# RLCD_SCH_28LED_v1p13p2.net
KiCad netlist of a schematic drawn in EAGLE
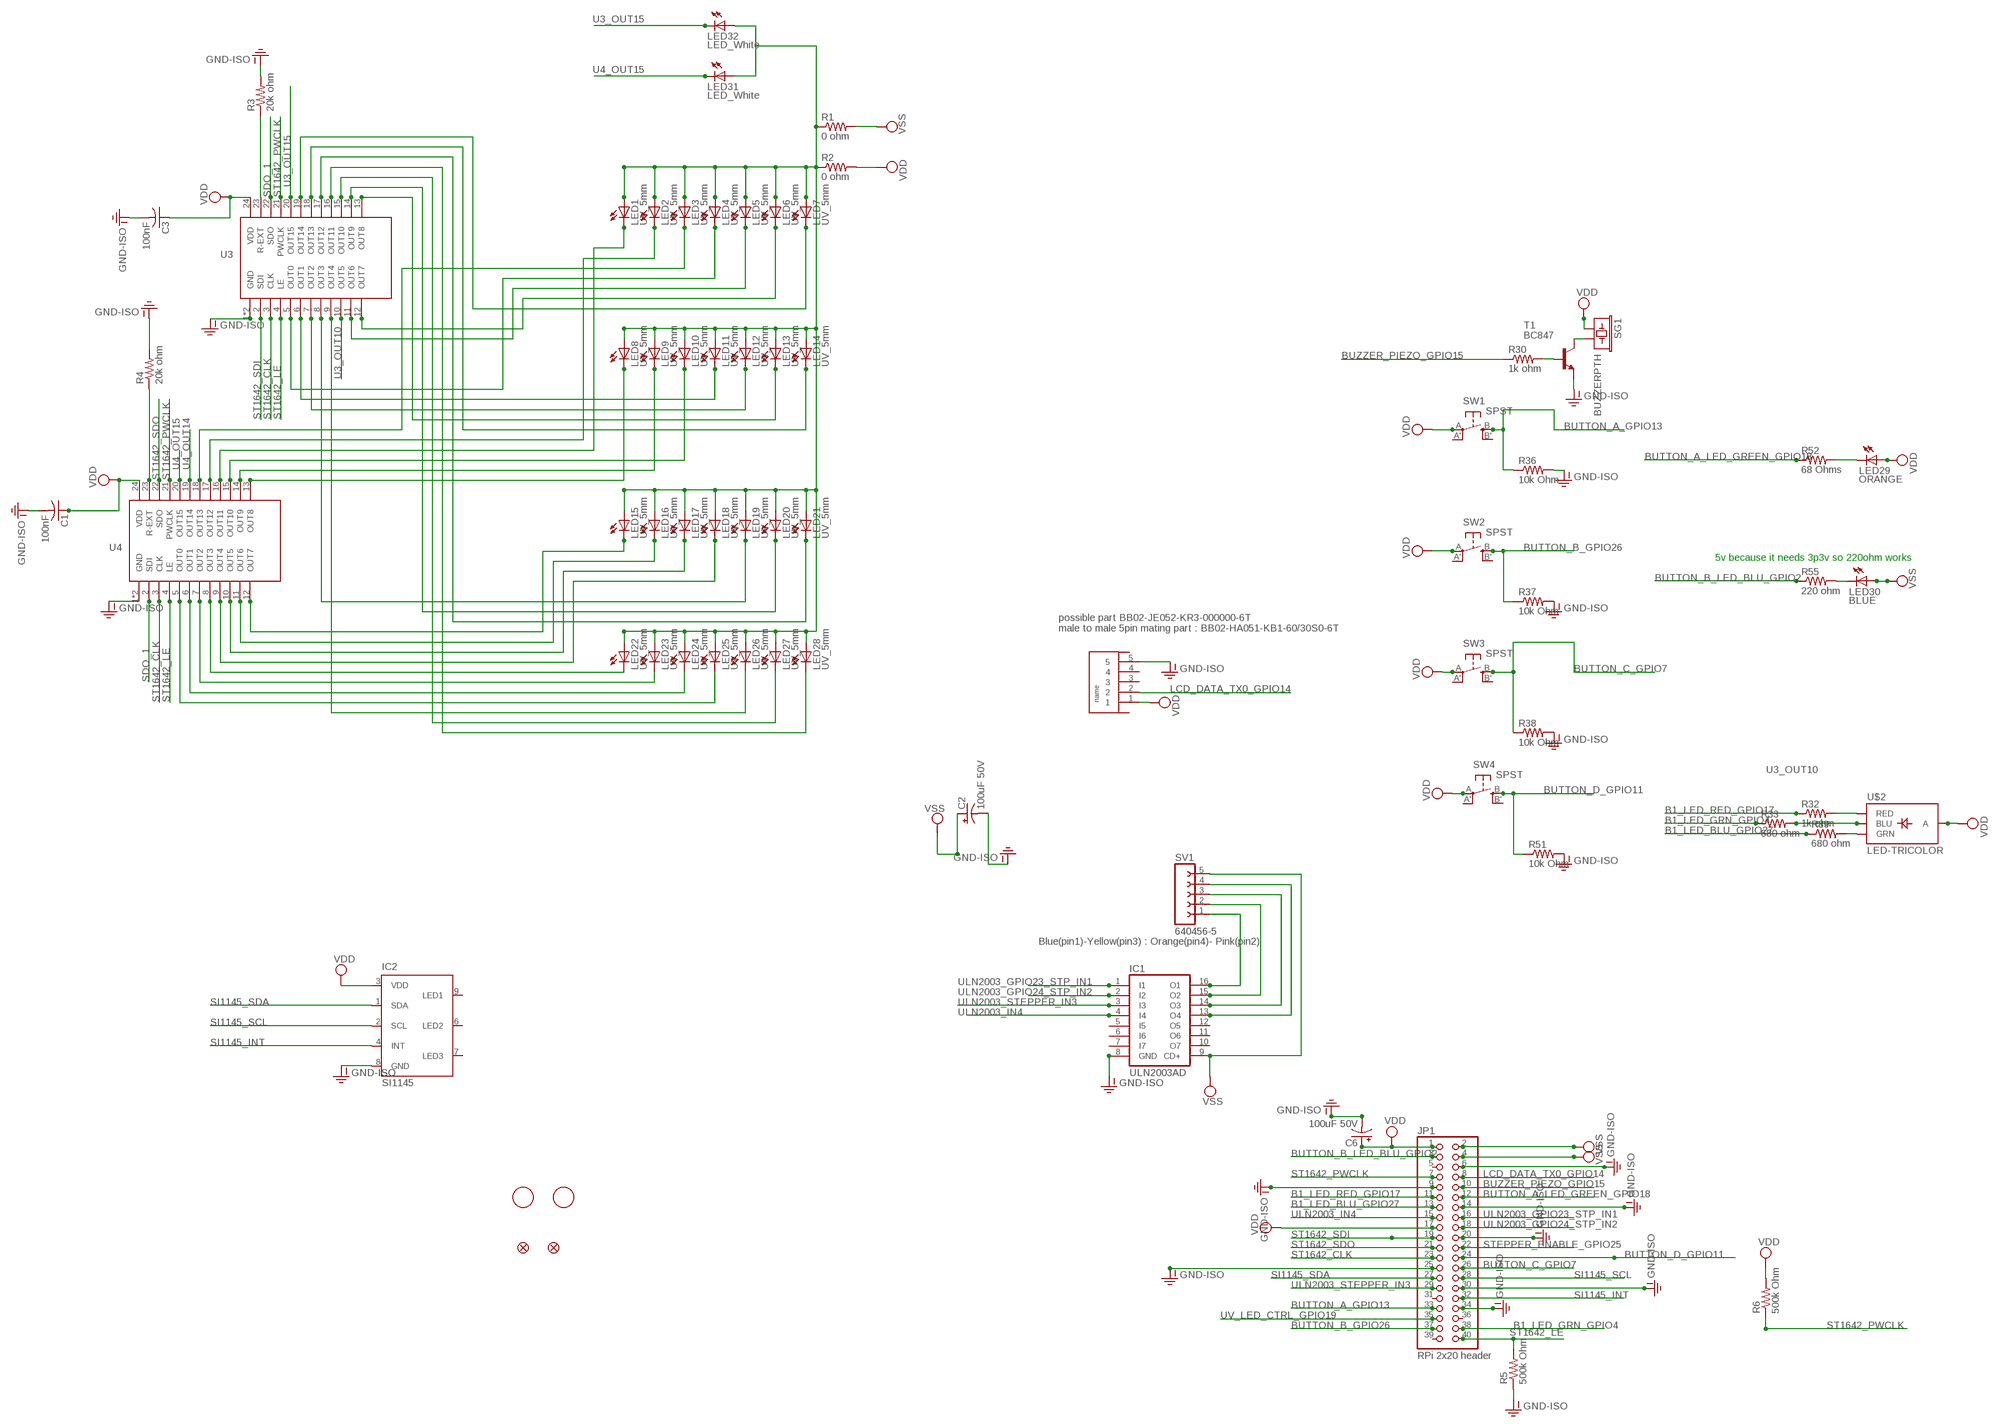
[diagram p0: schematic, sheet 1]

(export (version "E")
  (design (tool "Eeschema 10.0.6"))
  (components
    (comp (ref "C1")
      (value "100nF")
      (footprint "eagle-import:C0805")
      (libsource (lib "eagle-import") (part "C-USC0805"))
    )
    (comp (ref "C2")
      (value "100uF 50V")
      (footprint "eagle-import:E3,5-8")
      (fields (field (name "PARTNO") "REA101M1HBK-0811P"))
      (libsource (lib "eagle-import") (part "CPOL-USE3.5-8"))
    )
    (comp (ref "C3")
      (value "100nF")
      (footprint "eagle-import:C0805")
      (libsource (lib "eagle-import") (part "C-USC0805"))
    )
    (comp (ref "C6")
      (value "100uF 50V")
      (footprint "eagle-import:E3,5-8")
      (fields (field (name "PARTNO") "REA101M1HBK-0811P"))
      (libsource (lib "eagle-import") (part "CPOL-USE3.5-8"))
    )
    (comp (ref "FID1")
      (value "FIDUCIAL1X2")
      (footprint "eagle-import:FIDUCIAL-1X2")
      (libsource (lib "eagle-import") (part "FIDUCIAL1X2"))
    )
    (comp (ref "FID2")
      (value "FIDUCIAL1X2")
      (footprint "eagle-import:FIDUCIAL-1X2")
      (libsource (lib "eagle-import") (part "FIDUCIAL1X2"))
    )
    (comp (ref "IC1")
      (value "ULN2003AD")
      (footprint "eagle-import:SO16")
      (libsource (lib "eagle-import") (part "ULN2003AD"))
    )
    (comp (ref "IC2")
      (value "SI1145")
      (footprint "eagle-import:QFN-10")
      (libsource (lib "eagle-import") (part "SI1145"))
    )
    (comp (ref "JP1")
      (value "RPi 2x20 header")
      (footprint "eagle-import:2X20")
      (fields (field (name "PARTNO") "929975-01-13-RK"))
      (libsource (lib "eagle-import") (part "PINHD-2X20"))
    )
    (comp (ref "LED1")
      (value "UV_5mm")
      (footprint "eagle-import:LED5MM")
      (libsource (lib "eagle-import") (part "led_LED5MM"))
    )
    (comp (ref "LED2")
      (value "UV_5mm")
      (footprint "eagle-import:LED5MM")
      (libsource (lib "eagle-import") (part "led_LED5MM"))
    )
    (comp (ref "LED3")
      (value "UV_5mm")
      (footprint "eagle-import:LED5MM")
      (libsource (lib "eagle-import") (part "led_LED5MM"))
    )
    (comp (ref "LED4")
      (value "UV_5mm")
      (footprint "eagle-import:LED5MM")
      (libsource (lib "eagle-import") (part "led_LED5MM"))
    )
    (comp (ref "LED5")
      (value "UV_5mm")
      (footprint "eagle-import:LED5MM")
      (libsource (lib "eagle-import") (part "led_LED5MM"))
    )
    (comp (ref "LED6")
      (value "UV_5mm")
      (footprint "eagle-import:LED5MM")
      (libsource (lib "eagle-import") (part "led_LED5MM"))
    )
    (comp (ref "LED7")
      (value "UV_5mm")
      (footprint "eagle-import:LED5MM")
      (libsource (lib "eagle-import") (part "led_LED5MM"))
    )
    (comp (ref "LED8")
      (value "UV_5mm")
      (footprint "eagle-import:LED5MM")
      (libsource (lib "eagle-import") (part "led_LED5MM"))
    )
    (comp (ref "LED9")
      (value "UV_5mm")
      (footprint "eagle-import:LED5MM")
      (libsource (lib "eagle-import") (part "led_LED5MM"))
    )
    (comp (ref "LED10")
      (value "UV_5mm")
      (footprint "eagle-import:LED5MM")
      (libsource (lib "eagle-import") (part "led_LED5MM"))
    )
    (comp (ref "LED11")
      (value "UV_5mm")
      (footprint "eagle-import:LED5MM")
      (libsource (lib "eagle-import") (part "led_LED5MM"))
    )
    (comp (ref "LED12")
      (value "UV_5mm")
      (footprint "eagle-import:LED5MM")
      (libsource (lib "eagle-import") (part "led_LED5MM"))
    )
    (comp (ref "LED13")
      (value "UV_5mm")
      (footprint "eagle-import:LED5MM")
      (libsource (lib "eagle-import") (part "led_LED5MM"))
    )
    (comp (ref "LED14")
      (value "UV_5mm")
      (footprint "eagle-import:LED5MM")
      (libsource (lib "eagle-import") (part "led_LED5MM"))
    )
    (comp (ref "LED15")
      (value "UV_5mm")
      (footprint "eagle-import:LED5MM")
      (libsource (lib "eagle-import") (part "led_LED5MM"))
    )
    (comp (ref "LED16")
      (value "UV_5mm")
      (footprint "eagle-import:LED5MM")
      (libsource (lib "eagle-import") (part "led_LED5MM"))
    )
    (comp (ref "LED17")
      (value "UV_5mm")
      (footprint "eagle-import:LED5MM")
      (libsource (lib "eagle-import") (part "led_LED5MM"))
    )
    (comp (ref "LED18")
      (value "UV_5mm")
      (footprint "eagle-import:LED5MM")
      (libsource (lib "eagle-import") (part "led_LED5MM"))
    )
    (comp (ref "LED19")
      (value "UV_5mm")
      (footprint "eagle-import:LED5MM")
      (libsource (lib "eagle-import") (part "led_LED5MM"))
    )
    (comp (ref "LED20")
      (value "UV_5mm")
      (footprint "eagle-import:LED5MM")
      (libsource (lib "eagle-import") (part "led_LED5MM"))
    )
    (comp (ref "LED21")
      (value "UV_5mm")
      (footprint "eagle-import:LED5MM")
      (libsource (lib "eagle-import") (part "led_LED5MM"))
    )
    (comp (ref "LED22")
      (value "UV_5mm")
      (footprint "eagle-import:LED5MM")
      (libsource (lib "eagle-import") (part "led_LED5MM"))
    )
    (comp (ref "LED23")
      (value "UV_5mm")
      (footprint "eagle-import:LED5MM")
      (libsource (lib "eagle-import") (part "led_LED5MM"))
    )
    (comp (ref "LED24")
      (value "UV_5mm")
      (footprint "eagle-import:LED5MM")
      (libsource (lib "eagle-import") (part "led_LED5MM"))
    )
    (comp (ref "LED25")
      (value "UV_5mm")
      (footprint "eagle-import:LED5MM")
      (libsource (lib "eagle-import") (part "led_LED5MM"))
    )
    (comp (ref "LED26")
      (value "UV_5mm")
      (footprint "eagle-import:LED5MM")
      (libsource (lib "eagle-import") (part "led_LED5MM"))
    )
    (comp (ref "LED27")
      (value "UV_5mm")
      (footprint "eagle-import:LED5MM")
      (libsource (lib "eagle-import") (part "led_LED5MM"))
    )
    (comp (ref "LED28")
      (value "UV_5mm")
      (footprint "eagle-import:LED5MM")
      (libsource (lib "eagle-import") (part "led_LED5MM"))
    )
    (comp (ref "LED29")
      (value "ORANGE")
      (footprint "eagle-import:CHIPLED_1206")
      (fields (field (name "PARTNO") "LG N971-KN-1"))
      (libsource (lib "eagle-import") (part "LEDCHIPLED_1206"))
    )
    (comp (ref "LED30")
      (value "BLUE")
      (footprint "eagle-import:CHIPLED_1206")
      (fields (field (name "PARTNO") "LTST-C21TBKT"))
      (libsource (lib "eagle-import") (part "LEDCHIPLED_1206"))
    )
    (comp (ref "LED31")
      (value "LED_White")
      (footprint "eagle-import:CHIPLED_1206")
      (fields (field (name "PARTNO") "LG N971-KN-1"))
      (libsource (lib "eagle-import") (part "LEDCHIPLED_1206"))
    )
    (comp (ref "LED32")
      (value "LED_White")
      (footprint "eagle-import:CHIPLED_1206")
      (fields (field (name "PARTNO") "LG N971-KN-1"))
      (libsource (lib "eagle-import") (part "LEDCHIPLED_1206"))
    )
    (comp (ref "R1")
      (value "0 ohm")
      (footprint "eagle-import:0805")
      (fields (field (name "PARTNO") "DNP"))
      (libsource (lib "eagle-import") (part "RESISTOR0805-RES"))
    )
    (comp (ref "R2")
      (value "0 ohm")
      (footprint "eagle-import:0805")
      (fields (field (name "PARTNO") "DNP"))
      (libsource (lib "eagle-import") (part "RESISTOR0805-RES"))
    )
    (comp (ref "R3")
      (value "20k ohm")
      (footprint "eagle-import:0805")
      (fields (field (name "PARTNO") "DNP"))
      (libsource (lib "eagle-import") (part "RESISTOR0805-RES"))
    )
    (comp (ref "R4")
      (value "20k ohm")
      (footprint "eagle-import:0805")
      (fields (field (name "PARTNO") "DNP"))
      (libsource (lib "eagle-import") (part "RESISTOR0805-RES"))
    )
    (comp (ref "R5")
      (value "500k Ohm")
      (footprint "eagle-import:0805")
      (fields (field (name "PARTNO") "RK73B2ATTD103J"))
      (libsource (lib "eagle-import") (part "RESISTOR0805-RES"))
    )
    (comp (ref "R6")
      (value "500k Ohm")
      (footprint "eagle-import:0805")
      (fields (field (name "PARTNO") "RK73B2ATTD103J"))
      (libsource (lib "eagle-import") (part "RESISTOR0805-RES"))
    )
    (comp (ref "R30")
      (value "1k ohm")
      (footprint "eagle-import:0805")
      (fields (field (name "PARTNO") "RK73H2ATTD1001F"))
      (libsource (lib "eagle-import") (part "RESISTOR0805-RES"))
    )
    (comp (ref "R32")
      (value "1k ohm")
      (footprint "eagle-import:0805")
      (fields (field (name "PARTNO") "RK73H2ATTD1001F"))
      (libsource (lib "eagle-import") (part "RESISTOR0805-RES"))
    )
    (comp (ref "R33")
      (value "680 ohm")
      (footprint "eagle-import:0805")
      (fields (field (name "PARTNO") "RK73B2ATTD681J"))
      (libsource (lib "eagle-import") (part "RESISTOR0805-RES"))
    )
    (comp (ref "R36")
      (value "10k Ohm")
      (footprint "eagle-import:0805")
      (fields (field (name "PARTNO") "RK73B2ATTD103J"))
      (libsource (lib "eagle-import") (part "RESISTOR0805-RES"))
    )
    (comp (ref "R37")
      (value "10k Ohm")
      (footprint "eagle-import:0805")
      (fields (field (name "PARTNO") "RK73B2ATTD103J"))
      (libsource (lib "eagle-import") (part "RESISTOR0805-RES"))
    )
    (comp (ref "R38")
      (value "10k Ohm")
      (footprint "eagle-import:0805")
      (fields (field (name "PARTNO") "RK73B2ATTD103J"))
      (libsource (lib "eagle-import") (part "RESISTOR0805-RES"))
    )
    (comp (ref "R39")
      (value "680 ohm")
      (footprint "eagle-import:0805")
      (fields (field (name "PARTNO") "RK73B2ATTD681J"))
      (libsource (lib "eagle-import") (part "RESISTOR0805-RES"))
    )
    (comp (ref "R51")
      (value "10k Ohm")
      (footprint "eagle-import:0805")
      (fields (field (name "PARTNO") "RK73B2ATTD103J"))
      (libsource (lib "eagle-import") (part "RESISTOR0805-RES"))
    )
    (comp (ref "R52")
      (value "68 Ohms")
      (footprint "eagle-import:0805")
      (fields (field (name "PARTNO") "RK73B2ATTDD121J"))
      (libsource (lib "eagle-import") (part "RESISTOR0805-RES"))
    )
    (comp (ref "R55")
      (value "220 ohm")
      (footprint "eagle-import:0805")
      (fields (field (name "PARTNO") "RK73B2ATTD221J"))
      (libsource (lib "eagle-import") (part "RESISTOR0805-RES"))
    )
    (comp (ref "SG1")
      (value "BUZZERPTH")
      (footprint "eagle-import:BUZZER-12MM")
      (fields (field (name "PARTNO") "AT-1220-TT-R"))
      (libsource (lib "eagle-import") (part "BUZZERPTH"))
    )
    (comp (ref "SV1")
      (value "640456-5")
      (footprint "eagle-import:FE05-1")
      (libsource (lib "eagle-import") (part "FE05-1"))
    )
    (comp (ref "SV3_LCD_HEADER")
      (value "22-05-2051")
      (footprint "eagle-import:MDF7-5S-2.54DSA")
      (fields (field (name "PARTNO") "MDF7-5S-2.54DSA(55)"))
      (libsource (lib "eagle-import") (part "MDF7-5S-2.54DSA"))
    )
    (comp (ref "SW1")
      (value "SPST")
      (footprint "eagle-import:EVQ-Q2")
      (libsource (lib "eagle-import") (part "SPST_TACT-EVQQ2"))
    )
    (comp (ref "SW2")
      (value "SPST")
      (footprint "eagle-import:EVQ-Q2")
      (libsource (lib "eagle-import") (part "SPST_TACT-EVQQ2"))
    )
    (comp (ref "SW3")
      (value "SPST")
      (footprint "eagle-import:EVQ-Q2")
      (libsource (lib "eagle-import") (part "SPST_TACT-EVQQ2"))
    )
    (comp (ref "SW4")
      (value "SPST")
      (footprint "eagle-import:EVQ-Q2")
      (libsource (lib "eagle-import") (part "SPST_TACT-EVQQ2"))
    )
    (comp (ref "T1")
      (value "BC847")
      (footprint "eagle-import:SOT23")
      (fields (field (name "PARTNO") "MMUN2214LT1G"))
      (libsource (lib "eagle-import") (part "BC847"))
    )
    (comp (ref "U$1")
      (value "FIDUCIAL")
      (footprint "eagle-import:FIDUCIAL_1MM")
      (libsource (lib "eagle-import") (part "FIDUCIAL"))
    )
    (comp (ref "U$2")
      (value "LED-TRICOLOR")
      (footprint "eagle-import:LED-TRICOLOR-SMD")
      (fields (field (name "PARTNO") "CLV1A-FKB-CHMKPEHBB7A363"))
      (libsource (lib "eagle-import") (part "LED-TRICOLOR"))
    )
    (comp (ref "U$3")
      (value "LED1642GWTTR")
      (footprint "eagle-import:TSSOP24")
      (libsource (lib "eagle-import") (part "LED1642GWTTR"))
    )
    (comp (ref "U$4")
      (value "LED1642GWTTR")
      (footprint "eagle-import:TSSOP24")
      (libsource (lib "eagle-import") (part "LED1642GWTTR"))
    )
    (comp (ref "U$5")
      (value "FIDUCIAL")
      (footprint "eagle-import:FIDUCIAL_1MM")
      (libsource (lib "eagle-import") (part "FIDUCIAL"))
    )
  )
  (nets
    (net (code "1") (name "/B1_LED_BLU_GPIO27") (class "Default")
      (node (ref "JP1") (pin "13") (pinfunction "13_13") (pintype "passive"))
      (node (ref "R39") (pin "1") (pinfunction "1_1") (pintype "passive"))
    )
    (net (code "2") (name "/B1_LED_GRN_GPIO4") (class "Default")
      (node (ref "JP1") (pin "38") (pinfunction "38_38") (pintype "passive"))
      (node (ref "R33") (pin "1") (pinfunction "1_1") (pintype "passive"))
    )
    (net (code "3") (name "/B1_LED_RED_GPIO17") (class "Default")
      (node (ref "JP1") (pin "11") (pinfunction "11_11") (pintype "passive"))
      (node (ref "R32") (pin "1") (pinfunction "1_1") (pintype "passive"))
    )
    (net (code "4") (name "/BUTTON_A_GPIO13") (class "Default")
      (node (ref "JP1") (pin "33") (pinfunction "33_33") (pintype "passive"))
      (node (ref "R36") (pin "1") (pinfunction "1_1") (pintype "passive"))
      (node (ref "SW1") (pin "B") (pinfunction "S_B") (pintype "passive"))
    )
    (net (code "5") (name "/BUTTON_A_LED_GREEN_GPIO18") (class "Default")
      (node (ref "JP1") (pin "12") (pinfunction "12_12") (pintype "passive"))
      (node (ref "R52") (pin "1") (pinfunction "1_1") (pintype "passive"))
    )
    (net (code "6") (name "/BUTTON_B_GPIO26") (class "Default")
      (node (ref "JP1") (pin "37") (pinfunction "37_37") (pintype "passive"))
      (node (ref "R37") (pin "1") (pinfunction "1_1") (pintype "passive"))
      (node (ref "SW2") (pin "B") (pinfunction "S_B") (pintype "passive"))
    )
    (net (code "7") (name "/BUTTON_B_LED_BLU_GPIO2") (class "Default")
      (node (ref "JP1") (pin "3") (pinfunction "3_3") (pintype "passive"))
      (node (ref "R55") (pin "1") (pinfunction "1_1") (pintype "passive"))
    )
    (net (code "8") (name "/BUTTON_C_GPIO7") (class "Default")
      (node (ref "JP1") (pin "26") (pinfunction "26_26") (pintype "passive"))
      (node (ref "R38") (pin "1") (pinfunction "1_1") (pintype "passive"))
      (node (ref "SW3") (pin "B") (pinfunction "S_B") (pintype "passive"))
    )
    (net (code "9") (name "/BUTTON_D_GPIO11") (class "Default")
      (node (ref "JP1") (pin "24") (pinfunction "24_24") (pintype "passive"))
      (node (ref "R51") (pin "1") (pinfunction "1_1") (pintype "passive"))
      (node (ref "SW4") (pin "B") (pinfunction "S_B") (pintype "passive"))
    )
    (net (code "10") (name "/BUZZER_PIEZO_GPIO15") (class "Default")
      (node (ref "JP1") (pin "10") (pinfunction "10_10") (pintype "passive"))
      (node (ref "R30") (pin "1") (pinfunction "1_1") (pintype "passive"))
    )
    (net (code "11") (name "/LCD_DATA_TX0_GPIO14") (class "Default")
      (node (ref "JP1") (pin "8") (pinfunction "8_8") (pintype "passive"))
      (node (ref "SV3_LCD_HEADER") (pin "2") (pinfunction "2_2") (pintype "bidirectional"))
    )
    (net (code "12") (name "/SDO_1") (class "Default")
      (node (ref "U$3") (pin "22") (pinfunction "SDO_22") (pintype "bidirectional"))
      (node (ref "U$4") (pin "2") (pinfunction "SDI_2") (pintype "bidirectional"))
    )
    (net (code "13") (name "/SI1145_INT") (class "Default")
      (node (ref "IC2") (pin "4") (pinfunction "INT_4") (pintype "open_collector"))
      (node (ref "JP1") (pin "32") (pinfunction "32_32") (pintype "passive"))
    )
    (net (code "14") (name "/SI1145_SCL") (class "Default")
      (node (ref "IC2") (pin "2") (pinfunction "SCL_2") (pintype "input"))
      (node (ref "JP1") (pin "28") (pinfunction "28_28") (pintype "passive"))
    )
    (net (code "15") (name "/SI1145_SDA") (class "Default")
      (node (ref "IC2") (pin "1") (pinfunction "SDA_1") (pintype "bidirectional"))
      (node (ref "JP1") (pin "27") (pinfunction "27_27") (pintype "passive"))
    )
    (net (code "16") (name "/ST1642_CLK") (class "Default")
      (node (ref "JP1") (pin "23") (pinfunction "23_23") (pintype "passive"))
      (node (ref "U$3") (pin "3") (pinfunction "CLK_3") (pintype "bidirectional"))
      (node (ref "U$4") (pin "3") (pinfunction "CLK_3") (pintype "bidirectional"))
    )
    (net (code "17") (name "/ST1642_LE") (class "Default")
      (node (ref "JP1") (pin "40") (pinfunction "40_40") (pintype "passive"))
      (node (ref "R5") (pin "2") (pinfunction "2_2") (pintype "passive"))
      (node (ref "U$3") (pin "4") (pinfunction "LE_4") (pintype "bidirectional"))
      (node (ref "U$4") (pin "4") (pinfunction "LE_4") (pintype "bidirectional"))
    )
    (net (code "18") (name "/ST1642_PWCLK") (class "Default")
      (node (ref "JP1") (pin "7") (pinfunction "7_7") (pintype "passive"))
      (node (ref "R6") (pin "1") (pinfunction "1_1") (pintype "passive"))
      (node (ref "U$3") (pin "21") (pinfunction "PWCLK_21") (pintype "bidirectional"))
      (node (ref "U$4") (pin "21") (pinfunction "PWCLK_21") (pintype "bidirectional"))
    )
    (net (code "19") (name "/ST1642_SDI") (class "Default")
      (node (ref "JP1") (pin "19") (pinfunction "19_19") (pintype "passive"))
      (node (ref "U$3") (pin "2") (pinfunction "SDI_2") (pintype "bidirectional"))
    )
    (net (code "20") (name "/ST1642_SDO") (class "Default")
      (node (ref "JP1") (pin "21") (pinfunction "21_21") (pintype "passive"))
      (node (ref "U$4") (pin "22") (pinfunction "SDO_22") (pintype "bidirectional"))
    )
    (net (code "21") (name "/STEPPER_ENABLE_GPIO25") (class "Default")
      (node (ref "JP1") (pin "22") (pinfunction "22_22") (pintype "passive"))
    )
    (net (code "22") (name "/U3_OUT10") (class "Default")
      (node (ref "R32") (pin "2") (pinfunction "2_2") (pintype "passive"))
      (node (ref "U$2") (pin "R") (pinfunction "RED_R") (pintype "bidirectional"))
      (node (ref "U$3") (pin "10") (pinfunction "OUT5_10") (pintype "bidirectional"))
    )
    (net (code "23") (name "/U3_OUT15") (class "Default")
      (node (ref "LED32") (pin "C") (pinfunction "C_C") (pintype "passive"))
      (node (ref "U$3") (pin "20") (pinfunction "OUT15_20") (pintype "bidirectional"))
    )
    (net (code "24") (name "/U4_OUT14") (class "Default")
      (node (ref "U$4") (pin "19") (pinfunction "OUT14_19") (pintype "bidirectional"))
    )
    (net (code "25") (name "/U4_OUT15") (class "Default")
      (node (ref "LED31") (pin "C") (pinfunction "C_C") (pintype "passive"))
      (node (ref "U$4") (pin "20") (pinfunction "OUT15_20") (pintype "bidirectional"))
    )
    (net (code "26") (name "/ULN2003_GPIO23_STP_IN1") (class "Default")
      (node (ref "IC1") (pin "1") (pinfunction "I1_1") (pintype "input"))
      (node (ref "JP1") (pin "16") (pinfunction "16_16") (pintype "passive"))
    )
    (net (code "27") (name "/ULN2003_GPIO24_STP_IN2") (class "Default")
      (node (ref "IC1") (pin "2") (pinfunction "I2_2") (pintype "input"))
      (node (ref "JP1") (pin "18") (pinfunction "18_18") (pintype "passive"))
    )
    (net (code "28") (name "/ULN2003_IN4") (class "Default")
      (node (ref "IC1") (pin "4") (pinfunction "I4_4") (pintype "input"))
      (node (ref "JP1") (pin "15") (pinfunction "15_15") (pintype "passive"))
    )
    (net (code "29") (name "/ULN2003_STEPPER_IN3") (class "Default")
      (node (ref "IC1") (pin "3") (pinfunction "I3_3") (pintype "input"))
      (node (ref "JP1") (pin "29") (pinfunction "29_29") (pintype "passive"))
    )
    (net (code "30") (name "/UV_LED_CTRL_GPIO19") (class "Default")
      (node (ref "JP1") (pin "35") (pinfunction "35_35") (pintype "passive"))
    )
    (net (code "31") (name "GND-ISO") (class "Default")
      (node (ref "C1") (pin "2") (pinfunction "2_2") (pintype "passive"))
      (node (ref "C2") (pin "-") (pinfunction "-_-") (pintype "passive"))
      (node (ref "C3") (pin "2") (pinfunction "2_2") (pintype "passive"))
      (node (ref "C6") (pin "-") (pinfunction "-_-") (pintype "passive"))
      (node (ref "IC1") (pin "8") (pinfunction "GND_8") (pintype "power_in"))
      (node (ref "IC2") (pin "8") (pinfunction "GND_8") (pintype "power_in"))
      (node (ref "JP1") (pin "14") (pinfunction "14_14") (pintype "passive"))
      (node (ref "JP1") (pin "20") (pinfunction "20_20") (pintype "passive"))
      (node (ref "JP1") (pin "25") (pinfunction "25_25") (pintype "passive"))
      (node (ref "JP1") (pin "30") (pinfunction "30_30") (pintype "passive"))
      (node (ref "JP1") (pin "34") (pinfunction "34_34") (pintype "passive"))
      (node (ref "JP1") (pin "6") (pinfunction "6_6") (pintype "passive"))
      (node (ref "JP1") (pin "9") (pinfunction "9_9") (pintype "passive"))
      (node (ref "R3") (pin "2") (pinfunction "2_2") (pintype "passive"))
      (node (ref "R36") (pin "2") (pinfunction "2_2") (pintype "passive"))
      (node (ref "R37") (pin "2") (pinfunction "2_2") (pintype "passive"))
      (node (ref "R38") (pin "2") (pinfunction "2_2") (pintype "passive"))
      (node (ref "R4") (pin "2") (pinfunction "2_2") (pintype "passive"))
      (node (ref "R5") (pin "1") (pinfunction "1_1") (pintype "passive"))
      (node (ref "R51") (pin "2") (pinfunction "2_2") (pintype "passive"))
      (node (ref "SV3_LCD_HEADER") (pin "5") (pinfunction "5_5") (pintype "bidirectional"))
      (node (ref "T1") (pin "2") (pinfunction "E_2") (pintype "passive"))
      (node (ref "U$3") (pin "1") (pinfunction "GND_1") (pintype "bidirectional"))
      (node (ref "U$3") (pin "P$100") (pinfunction "GND_P$100") (pintype "bidirectional"))
      (node (ref "U$4") (pin "1") (pinfunction "GND_1") (pintype "bidirectional"))
      (node (ref "U$4") (pin "P$100") (pinfunction "GND_P$100") (pintype "bidirectional"))
    )
    (net (code "32") (name "Net-(IC1-O1)") (class "Default")
      (node (ref "IC1") (pin "16") (pinfunction "O1_16") (pintype "open_collector"))
      (node (ref "SV1") (pin "1") (pinfunction "1_1") (pintype "passive"))
    )
    (net (code "33") (name "Net-(IC1-O2)") (class "Default")
      (node (ref "IC1") (pin "15") (pinfunction "O2_15") (pintype "open_collector"))
      (node (ref "SV1") (pin "2") (pinfunction "2_2") (pintype "passive"))
    )
    (net (code "34") (name "Net-(IC1-O3)") (class "Default")
      (node (ref "IC1") (pin "14") (pinfunction "O3_14") (pintype "open_collector"))
      (node (ref "SV1") (pin "3") (pinfunction "3_3") (pintype "passive"))
    )
    (net (code "35") (name "Net-(IC1-O4)") (class "Default")
      (node (ref "IC1") (pin "13") (pinfunction "O4_13") (pintype "open_collector"))
      (node (ref "SV1") (pin "4") (pinfunction "4_4") (pintype "passive"))
    )
    (net (code "36") (name "Net-(LED1-C)") (class "Default")
      (node (ref "LED1") (pin "K") (pinfunction "C_K") (pintype "passive"))
      (node (ref "U$4") (pin "16") (pinfunction "OUT11_16") (pintype "bidirectional"))
    )
    (net (code "37") (name "Net-(LED1-PadA)") (class "Default")
      (node (ref "LED1") (pin "A") (pinfunction "A_A") (pintype "passive"))
      (node (ref "LED10") (pin "A") (pinfunction "A_A") (pintype "passive"))
      (node (ref "LED11") (pin "A") (pinfunction "A_A") (pintype "passive"))
      (node (ref "LED12") (pin "A") (pinfunction "A_A") (pintype "passive"))
      (node (ref "LED13") (pin "A") (pinfunction "A_A") (pintype "passive"))
      (node (ref "LED14") (pin "A") (pinfunction "A_A") (pintype "passive"))
      (node (ref "LED15") (pin "A") (pinfunction "A_A") (pintype "passive"))
      (node (ref "LED16") (pin "A") (pinfunction "A_A") (pintype "passive"))
      (node (ref "LED17") (pin "A") (pinfunction "A_A") (pintype "passive"))
      (node (ref "LED18") (pin "A") (pinfunction "A_A") (pintype "passive"))
      (node (ref "LED19") (pin "A") (pinfunction "A_A") (pintype "passive"))
      (node (ref "LED2") (pin "A") (pinfunction "A_A") (pintype "passive"))
      (node (ref "LED20") (pin "A") (pinfunction "A_A") (pintype "passive"))
      (node (ref "LED21") (pin "A") (pinfunction "A_A") (pintype "passive"))
      (node (ref "LED22") (pin "A") (pinfunction "A_A") (pintype "passive"))
      (node (ref "LED23") (pin "A") (pinfunction "A_A") (pintype "passive"))
      (node (ref "LED24") (pin "A") (pinfunction "A_A") (pintype "passive"))
      (node (ref "LED25") (pin "A") (pinfunction "A_A") (pintype "passive"))
      (node (ref "LED26") (pin "A") (pinfunction "A_A") (pintype "passive"))
      (node (ref "LED27") (pin "A") (pinfunction "A_A") (pintype "passive"))
      (node (ref "LED28") (pin "A") (pinfunction "A_A") (pintype "passive"))
      (node (ref "LED3") (pin "A") (pinfunction "A_A") (pintype "passive"))
      (node (ref "LED31") (pin "A") (pinfunction "A_A") (pintype "passive"))
      (node (ref "LED32") (pin "A") (pinfunction "A_A") (pintype "passive"))
      (node (ref "LED4") (pin "A") (pinfunction "A_A") (pintype "passive"))
      (node (ref "LED5") (pin "A") (pinfunction "A_A") (pintype "passive"))
      (node (ref "LED6") (pin "A") (pinfunction "A_A") (pintype "passive"))
      (node (ref "LED7") (pin "A") (pinfunction "A_A") (pintype "passive"))
      (node (ref "LED8") (pin "A") (pinfunction "A_A") (pintype "passive"))
      (node (ref "LED9") (pin "A") (pinfunction "A_A") (pintype "passive"))
      (node (ref "R1") (pin "1") (pinfunction "1_1") (pintype "passive"))
      (node (ref "R2") (pin "1") (pinfunction "1_1") (pintype "passive"))
    )
    (net (code "38") (name "Net-(LED2-C)") (class "Default")
      (node (ref "LED2") (pin "K") (pinfunction "C_K") (pintype "passive"))
      (node (ref "U$4") (pin "17") (pinfunction "OUT12_17") (pintype "bidirectional"))
    )
    (net (code "39") (name "Net-(LED3-C)") (class "Default")
      (node (ref "LED3") (pin "K") (pinfunction "C_K") (pintype "passive"))
      (node (ref "U$4") (pin "18") (pinfunction "OUT13_18") (pintype "bidirectional"))
    )
    (net (code "40") (name "Net-(LED4-C)") (class "Default")
      (node (ref "LED4") (pin "K") (pinfunction "C_K") (pintype "passive"))
      (node (ref "U$3") (pin "5") (pinfunction "OUT0_5") (pintype "bidirectional"))
    )
    (net (code "41") (name "Net-(LED5-C)") (class "Default")
      (node (ref "LED5") (pin "K") (pinfunction "C_K") (pintype "passive"))
      (node (ref "U$3") (pin "11") (pinfunction "OUT6_11") (pintype "bidirectional"))
    )
    (net (code "42") (name "Net-(LED6-C)") (class "Default")
      (node (ref "LED6") (pin "K") (pinfunction "C_K") (pintype "passive"))
      (node (ref "U$3") (pin "12") (pinfunction "OUT7_12") (pintype "bidirectional"))
    )
    (net (code "43") (name "Net-(LED7-C)") (class "Default")
      (node (ref "LED7") (pin "K") (pinfunction "C_K") (pintype "passive"))
      (node (ref "U$3") (pin "19") (pinfunction "OUT14_19") (pintype "bidirectional"))
    )
    (net (code "44") (name "Net-(LED8-C)") (class "Default")
      (node (ref "LED8") (pin "K") (pinfunction "C_K") (pintype "passive"))
      (node (ref "U$4") (pin "13") (pinfunction "OUT8_13") (pintype "bidirectional"))
    )
    (net (code "45") (name "Net-(LED9-C)") (class "Default")
      (node (ref "LED9") (pin "K") (pinfunction "C_K") (pintype "passive"))
      (node (ref "U$4") (pin "14") (pinfunction "OUT9_14") (pintype "bidirectional"))
    )
    (net (code "46") (name "Net-(LED10-C)") (class "Default")
      (node (ref "LED10") (pin "K") (pinfunction "C_K") (pintype "passive"))
      (node (ref "U$4") (pin "15") (pinfunction "OUT10_15") (pintype "bidirectional"))
    )
    (net (code "47") (name "Net-(LED11-C)") (class "Default")
      (node (ref "LED11") (pin "K") (pinfunction "C_K") (pintype "passive"))
      (node (ref "U$3") (pin "6") (pinfunction "OUT1_6") (pintype "bidirectional"))
    )
    (net (code "48") (name "Net-(LED12-C)") (class "Default")
      (node (ref "LED12") (pin "K") (pinfunction "C_K") (pintype "passive"))
      (node (ref "U$3") (pin "7") (pinfunction "OUT2_7") (pintype "bidirectional"))
    )
    (net (code "49") (name "Net-(LED13-C)") (class "Default")
      (node (ref "LED13") (pin "K") (pinfunction "C_K") (pintype "passive"))
      (node (ref "U$3") (pin "13") (pinfunction "OUT8_13") (pintype "bidirectional"))
    )
    (net (code "50") (name "Net-(LED14-C)") (class "Default")
      (node (ref "LED14") (pin "K") (pinfunction "C_K") (pintype "passive"))
      (node (ref "U$3") (pin "18") (pinfunction "OUT13_18") (pintype "bidirectional"))
    )
    (net (code "51") (name "Net-(LED15-C)") (class "Default")
      (node (ref "LED15") (pin "K") (pinfunction "C_K") (pintype "passive"))
      (node (ref "U$4") (pin "12") (pinfunction "OUT7_12") (pintype "bidirectional"))
    )
    (net (code "52") (name "Net-(LED16-C)") (class "Default")
      (node (ref "LED16") (pin "K") (pinfunction "C_K") (pintype "passive"))
      (node (ref "U$4") (pin "11") (pinfunction "OUT6_11") (pintype "bidirectional"))
    )
    (net (code "53") (name "Net-(LED17-C)") (class "Default")
      (node (ref "LED17") (pin "K") (pinfunction "C_K") (pintype "passive"))
      (node (ref "U$4") (pin "10") (pinfunction "OUT5_10") (pintype "bidirectional"))
    )
    (net (code "54") (name "Net-(LED18-C)") (class "Default")
      (node (ref "LED18") (pin "K") (pinfunction "C_K") (pintype "passive"))
      (node (ref "U$4") (pin "9") (pinfunction "OUT4_9") (pintype "bidirectional"))
    )
    (net (code "55") (name "Net-(LED19-C)") (class "Default")
      (node (ref "LED19") (pin "K") (pinfunction "C_K") (pintype "passive"))
      (node (ref "U$3") (pin "8") (pinfunction "OUT3_8") (pintype "bidirectional"))
    )
    (net (code "56") (name "Net-(LED20-C)") (class "Default")
      (node (ref "LED20") (pin "K") (pinfunction "C_K") (pintype "passive"))
      (node (ref "U$3") (pin "14") (pinfunction "OUT9_14") (pintype "bidirectional"))
    )
    (net (code "57") (name "Net-(LED21-C)") (class "Default")
      (node (ref "LED21") (pin "K") (pinfunction "C_K") (pintype "passive"))
      (node (ref "U$3") (pin "17") (pinfunction "OUT12_17") (pintype "bidirectional"))
    )
    (net (code "58") (name "Net-(LED22-C)") (class "Default")
      (node (ref "LED22") (pin "K") (pinfunction "C_K") (pintype "passive"))
      (node (ref "U$4") (pin "8") (pinfunction "OUT3_8") (pintype "bidirectional"))
    )
    (net (code "59") (name "Net-(LED23-C)") (class "Default")
      (node (ref "LED23") (pin "K") (pinfunction "C_K") (pintype "passive"))
      (node (ref "U$4") (pin "7") (pinfunction "OUT2_7") (pintype "bidirectional"))
    )
    (net (code "60") (name "Net-(LED24-C)") (class "Default")
      (node (ref "LED24") (pin "K") (pinfunction "C_K") (pintype "passive"))
      (node (ref "U$4") (pin "6") (pinfunction "OUT1_6") (pintype "bidirectional"))
    )
    (net (code "61") (name "Net-(LED25-C)") (class "Default")
      (node (ref "LED25") (pin "K") (pinfunction "C_K") (pintype "passive"))
      (node (ref "U$4") (pin "5") (pinfunction "OUT0_5") (pintype "bidirectional"))
    )
    (net (code "62") (name "Net-(LED26-C)") (class "Default")
      (node (ref "LED26") (pin "K") (pinfunction "C_K") (pintype "passive"))
      (node (ref "U$3") (pin "9") (pinfunction "OUT4_9") (pintype "bidirectional"))
    )
    (net (code "63") (name "Net-(LED27-C)") (class "Default")
      (node (ref "LED27") (pin "K") (pinfunction "C_K") (pintype "passive"))
      (node (ref "U$3") (pin "15") (pinfunction "OUT10_15") (pintype "bidirectional"))
    )
    (net (code "64") (name "Net-(LED28-C)") (class "Default")
      (node (ref "LED28") (pin "K") (pinfunction "C_K") (pintype "passive"))
      (node (ref "U$3") (pin "16") (pinfunction "OUT11_16") (pintype "bidirectional"))
    )
    (net (code "65") (name "Net-(LED29-PadC)") (class "Default")
      (node (ref "LED29") (pin "C") (pinfunction "C_C") (pintype "passive"))
      (node (ref "R52") (pin "2") (pinfunction "2_2") (pintype "passive"))
    )
    (net (code "66") (name "Net-(LED30-PadC)") (class "Default")
      (node (ref "LED30") (pin "C") (pinfunction "C_C") (pintype "passive"))
      (node (ref "R55") (pin "2") (pinfunction "2_2") (pintype "passive"))
    )
    (net (code "67") (name "Net-(SG1-2)") (class "Default")
      (node (ref "SG1") (pin "-") (pinfunction "2_-") (pintype "passive"))
      (node (ref "T1") (pin "3") (pinfunction "C_3") (pintype "passive"))
    )
    (net (code "68") (name "Net-(T1-B)") (class "Default")
      (node (ref "R30") (pin "2") (pinfunction "2_2") (pintype "passive"))
      (node (ref "T1") (pin "1") (pinfunction "B_1") (pintype "passive"))
    )
    (net (code "69") (name "Net-(U$2-BLU)") (class "Default")
      (node (ref "R33") (pin "2") (pinfunction "2_2") (pintype "passive"))
      (node (ref "U$2") (pin "B") (pinfunction "BLU_B") (pintype "bidirectional"))
    )
    (net (code "70") (name "Net-(U$2-GRN)") (class "Default")
      (node (ref "R39") (pin "2") (pinfunction "2_2") (pintype "passive"))
      (node (ref "U$2") (pin "G") (pinfunction "GRN_G") (pintype "bidirectional"))
    )
    (net (code "71") (name "Net-(U$3-R-EXT)") (class "Default")
      (node (ref "R3") (pin "1") (pinfunction "1_1") (pintype "passive"))
      (node (ref "U$3") (pin "23") (pinfunction "R-EXT_23") (pintype "bidirectional"))
    )
    (net (code "72") (name "Net-(U$4-R-EXT)") (class "Default")
      (node (ref "R4") (pin "1") (pinfunction "1_1") (pintype "passive"))
      (node (ref "U$4") (pin "23") (pinfunction "R-EXT_23") (pintype "bidirectional"))
    )
    (net (code "73") (name "VDD") (class "Default")
      (node (ref "C1") (pin "1") (pinfunction "1_1") (pintype "passive"))
      (node (ref "C3") (pin "1") (pinfunction "1_1") (pintype "passive"))
      (node (ref "C6") (pin "+") (pinfunction "+_+") (pintype "passive"))
      (node (ref "IC2") (pin "3") (pinfunction "VDD_3") (pintype "power_in"))
      (node (ref "JP1") (pin "1") (pinfunction "1_1") (pintype "passive"))
      (node (ref "JP1") (pin "17") (pinfunction "17_17") (pintype "passive"))
      (node (ref "LED29") (pin "A") (pinfunction "A_A") (pintype "passive"))
      (node (ref "R2") (pin "2") (pinfunction "2_2") (pintype "passive"))
      (node (ref "R6") (pin "2") (pinfunction "2_2") (pintype "passive"))
      (node (ref "SG1") (pin "+") (pinfunction "1_+") (pintype "passive"))
      (node (ref "SV3_LCD_HEADER") (pin "1") (pinfunction "1_1") (pintype "bidirectional"))
      (node (ref "SW1") (pin "A") (pinfunction "P_A") (pintype "passive"))
      (node (ref "SW2") (pin "A") (pinfunction "P_A") (pintype "passive"))
      (node (ref "SW3") (pin "A") (pinfunction "P_A") (pintype "passive"))
      (node (ref "SW4") (pin "A") (pinfunction "P_A") (pintype "passive"))
      (node (ref "U$2") (pin "A") (pinfunction "A_A") (pintype "bidirectional"))
      (node (ref "U$3") (pin "24") (pinfunction "VDD_24") (pintype "bidirectional"))
      (node (ref "U$4") (pin "24") (pinfunction "VDD_24") (pintype "bidirectional"))
    )
    (net (code "74") (name "VSS") (class "Default")
      (node (ref "C2") (pin "+") (pinfunction "+_+") (pintype "passive"))
      (node (ref "IC1") (pin "9") (pinfunction "CD+_9") (pintype "passive"))
      (node (ref "JP1") (pin "2") (pinfunction "2_2") (pintype "passive"))
      (node (ref "JP1") (pin "4") (pinfunction "4_4") (pintype "passive"))
      (node (ref "LED30") (pin "A") (pinfunction "A_A") (pintype "passive"))
      (node (ref "R1") (pin "2") (pinfunction "2_2") (pintype "passive"))
      (node (ref "SV1") (pin "5") (pinfunction "5_5") (pintype "passive"))
    )
    (net (code "75") (name "unconnected-(IC1-I5-Pad5)") (class "Default")
      (node (ref "IC1") (pin "5") (pinfunction "I5_5") (pintype "input"))
    )
    (net (code "76") (name "unconnected-(IC1-I6-Pad6)") (class "Default")
      (node (ref "IC1") (pin "6") (pinfunction "I6_6") (pintype "input"))
    )
    (net (code "77") (name "unconnected-(IC1-I7-Pad7)") (class "Default")
      (node (ref "IC1") (pin "7") (pinfunction "I7_7") (pintype "input"))
    )
    (net (code "78") (name "unconnected-(IC1-O5-Pad12)") (class "Default")
      (node (ref "IC1") (pin "12") (pinfunction "O5_12") (pintype "open_collector"))
    )
    (net (code "79") (name "unconnected-(IC1-O6-Pad11)") (class "Default")
      (node (ref "IC1") (pin "11") (pinfunction "O6_11") (pintype "open_collector"))
    )
    (net (code "80") (name "unconnected-(IC1-O7-Pad10)") (class "Default")
      (node (ref "IC1") (pin "10") (pinfunction "O7_10") (pintype "open_collector"))
    )
    (net (code "81") (name "unconnected-(IC2-LED1-Pad9)") (class "Default")
      (node (ref "IC2") (pin "9") (pinfunction "LED1_9") (pintype "output"))
    )
    (net (code "82") (name "unconnected-(IC2-LED2-Pad6)") (class "Default")
      (node (ref "IC2") (pin "6") (pinfunction "LED2_6") (pintype "output"))
    )
    (net (code "83") (name "unconnected-(IC2-LED3-Pad7)") (class "Default")
      (node (ref "IC2") (pin "7") (pinfunction "LED3_7") (pintype "output"))
    )
    (net (code "84") (name "unconnected-(JP1-Pad5)") (class "Default")
      (node (ref "JP1") (pin "5") (pinfunction "5_5") (pintype "passive"))
    )
    (net (code "85") (name "unconnected-(JP1-Pad31)") (class "Default")
      (node (ref "JP1") (pin "31") (pinfunction "31_31") (pintype "passive"))
    )
    (net (code "86") (name "unconnected-(JP1-Pad36)") (class "Default")
      (node (ref "JP1") (pin "36") (pinfunction "36_36") (pintype "passive"))
    )
    (net (code "87") (name "unconnected-(JP1-Pad39)") (class "Default")
      (node (ref "JP1") (pin "39") (pinfunction "39_39") (pintype "passive"))
    )
    (net (code "88") (name "unconnected-(SV3_LCD_HEADER-Pad3)") (class "Default")
      (node (ref "SV3_LCD_HEADER") (pin "3") (pinfunction "3_3") (pintype "bidirectional"))
    )
    (net (code "89") (name "unconnected-(SV3_LCD_HEADER-Pad4)") (class "Default")
      (node (ref "SV3_LCD_HEADER") (pin "4") (pinfunction "4_4") (pintype "bidirectional"))
    )
    (net (code "90") (name "unconnected-(SW1-P1-PadA')") (class "Default")
      (node (ref "SW1") (pin "A'") (pinfunction "P1_A'") (pintype "passive"))
    )
    (net (code "91") (name "unconnected-(SW1-S1-PadB')") (class "Default")
      (node (ref "SW1") (pin "B'") (pinfunction "S1_B'") (pintype "passive"))
    )
    (net (code "92") (name "unconnected-(SW2-P1-PadA')") (class "Default")
      (node (ref "SW2") (pin "A'") (pinfunction "P1_A'") (pintype "passive"))
    )
    (net (code "93") (name "unconnected-(SW2-S1-PadB')") (class "Default")
      (node (ref "SW2") (pin "B'") (pinfunction "S1_B'") (pintype "passive"))
    )
    (net (code "94") (name "unconnected-(SW3-P1-PadA')") (class "Default")
      (node (ref "SW3") (pin "A'") (pinfunction "P1_A'") (pintype "passive"))
    )
    (net (code "95") (name "unconnected-(SW3-S1-PadB')") (class "Default")
      (node (ref "SW3") (pin "B'") (pinfunction "S1_B'") (pintype "passive"))
    )
    (net (code "96") (name "unconnected-(SW4-P1-PadA')") (class "Default")
      (node (ref "SW4") (pin "A'") (pinfunction "P1_A'") (pintype "passive"))
    )
    (net (code "97") (name "unconnected-(SW4-S1-PadB')") (class "Default")
      (node (ref "SW4") (pin "B'") (pinfunction "S1_B'") (pintype "passive"))
    )
  )
)
